# CAN.net
KiCad netlist of a schematic drawn in Altium Designer
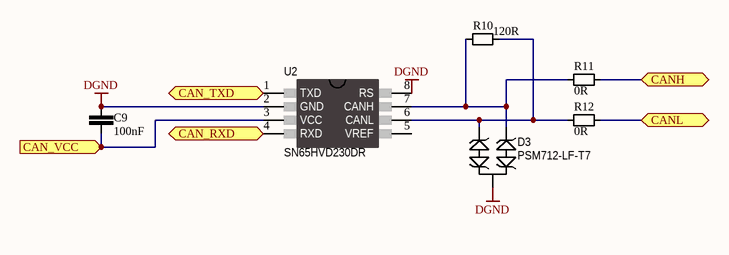
[diagram p0: CAN.SchDoc]

(export (version "E")
  (design (tool "Eeschema 10.0.6"))
  (components
    (comp (ref "C9")
      (value "100nF")
      (footprint "GreenBox:0603-C")
      (description "MLCC 100nF 10% 50V X7R 0603")
      (fields (field (name "Comment") "Cap") (field (name "PUBLISHER") "GreenBox"))
      (libsource (lib "Capacitor") (part "C21C100NK1H0"))
    )
    (comp (ref "D3")
      (value "PSM712-LF-T7")
      (footprint "GreenBox:SOT-23_N")
      (description "TVS PSM712-LF-T7 Vbr 7.5V, 13.3V Vc/Ipp 17V/34A, 30V/30A (3-1 3-2, 1-3 2-3)")
      (fields (field (name "MANUFACTURER") "PROTEK DEVICES") (field (name "PUBLISHER") "GreenBox"))
      (libsource (lib "Diode_Transistor") (part "DT42PSM712LK"))
    )
    (comp (ref "R10")
      (value "120R")
      (footprint "GreenBox:0603-R")
      (description "SMD Resistor 120R 1% 1/10W 0603 100PPM")
      (fields (field (name "Comment") "Res") (field (name "PUBLISHER") "GreenBox"))
      (libsource (lib "Resistor") (part "R11C120RFBF0"))
    )
    (comp (ref "R11")
      (value "0R")
      (footprint "GreenBox:0603-R")
      (description "SMD Resistor 0R 1% 1/10W 0603 100PPM")
      (fields (field (name "Comment") "Res") (field (name "PUBLISHER") "GreenBox"))
      (libsource (lib "Resistor") (part "R11C000RFBF0"))
    )
    (comp (ref "R12")
      (value "0R")
      (footprint "GreenBox:0603-R")
      (description "SMD Resistor 0R 1% 1/10W 0603 100PPM")
      (fields (field (name "Comment") "Res") (field (name "PUBLISHER") "GreenBox"))
      (libsource (lib "Resistor") (part "R11C000RFBF0"))
    )
    (comp (ref "U2")
      (value "SN65HVD230DR")
      (footprint "GreenBox:SO-8_N")
      (description "CAN Bus Transceivers SN65HVD230DR Vcc 3.3V")
      (fields (field (name "MANUFACTURER") "TEXAS INSTRUMENTS") (field (name "PUBLISHER") "GreenBox"))
      (libsource (lib "Semiconductor") (part "U2S1VD230DRT"))
    )
  )
  (nets
    (net (code "1") (name "/CANH") (class "Default")
      (node (ref "R11") (pin "2") (pinfunction "2_2") (pintype "passive"))
    )
    (net (code "2") (name "/CANL") (class "Default")
      (node (ref "R12") (pin "2") (pinfunction "2_2") (pintype "passive"))
    )
    (net (code "3") (name "/CAN_RXD") (class "Default")
      (node (ref "U2") (pin "4") (pinfunction "RXD_4") (pintype "passive"))
    )
    (net (code "4") (name "/CAN_TXD") (class "Default")
      (node (ref "U2") (pin "1") (pinfunction "TXD_1") (pintype "passive"))
    )
    (net (code "5") (name "/CAN_VCC") (class "Default")
      (node (ref "C9") (pin "1") (pinfunction "1_1") (pintype "passive"))
      (node (ref "U2") (pin "3") (pinfunction "VCC_3") (pintype "passive"))
    )
    (net (code "6") (name "DGND") (class "Default")
      (node (ref "C9") (pin "2") (pinfunction "2_2") (pintype "passive"))
      (node (ref "D3") (pin "3") (pinfunction "3_3") (pintype "passive"))
      (node (ref "U2") (pin "2") (pinfunction "GND_2") (pintype "passive"))
      (node (ref "U2") (pin "8") (pinfunction "RS_8") (pintype "passive"))
    )
    (net (code "7") (name "Net-(U2-CANH)") (class "Default")
      (node (ref "D3") (pin "1") (pinfunction "1_1") (pintype "passive"))
      (node (ref "R10") (pin "1") (pinfunction "1_1") (pintype "passive"))
      (node (ref "R11") (pin "1") (pinfunction "1_1") (pintype "passive"))
      (node (ref "U2") (pin "7") (pinfunction "CANH_7") (pintype "passive"))
    )
    (net (code "8") (name "Net-(U2-CANL)") (class "Default")
      (node (ref "D3") (pin "2") (pinfunction "2_2") (pintype "passive"))
      (node (ref "R10") (pin "2") (pinfunction "2_2") (pintype "passive"))
      (node (ref "R12") (pin "1") (pinfunction "1_1") (pintype "passive"))
      (node (ref "U2") (pin "6") (pinfunction "CANL_6") (pintype "passive"))
    )
    (net (code "9") (name "unconnected-(U2-VREF-Pad5)") (class "Default")
      (node (ref "U2") (pin "5") (pinfunction "VREF_5") (pintype "passive"))
    )
  )
)
